# RAB_FM_Birds_3_for_open_bus.net
KiCad netlist of a schematic drawn in EAGLE
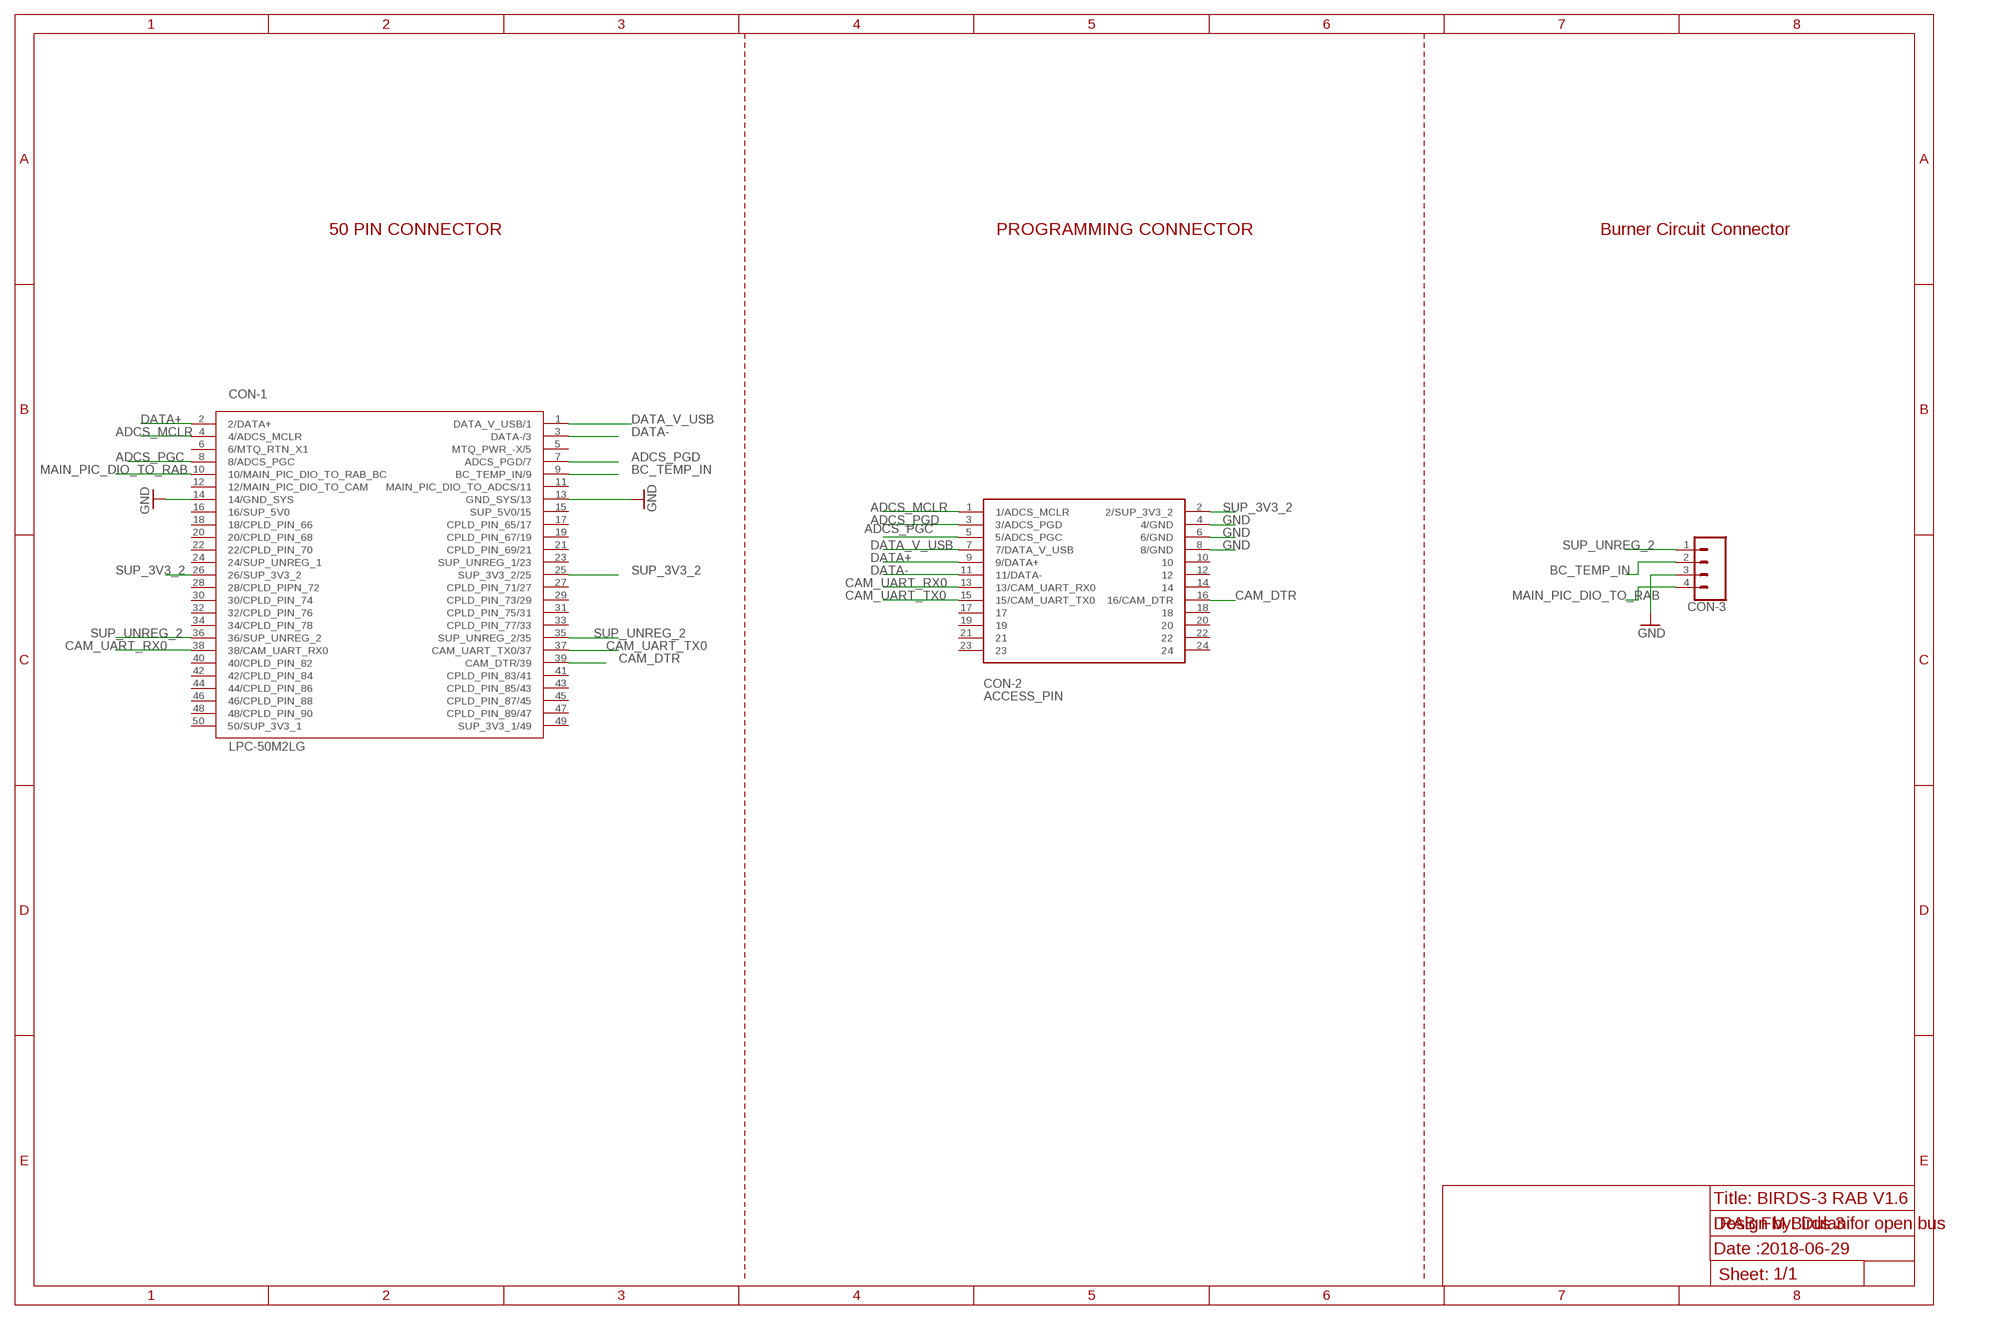
[diagram p0: schematic, sheet 1]

(export (version "E")
  (design (tool "Eeschema 10.0.6"))
  (components
    (comp (ref "CON-1")
      (value "LPC-50M2LG")
      (footprint "eagle-import:LPC-50M2LG")
      (libsource (lib "eagle-import") (part "LPC-50M2LG"))
    )
    (comp (ref "CON-2")
      (value "ACCESS_PIN")
      (footprint "eagle-import:SMD24")
      (libsource (lib "eagle-import") (part "ACCESS_PIN"))
    )
    (comp (ref "CON-3")
      (value "CONN_04JST-PTH")
      (footprint "eagle-import:JST-4-PTH")
      (libsource (lib "eagle-import") (part "CONN_04JST-PTH"))
    )
  )
  (nets
    (net (code "1") (name "/ADCS_MCLR") (class "Default")
      (node (ref "CON-1") (pin "4") (pinfunction "4/ADCS_MCLR_4") (pintype "bidirectional"))
      (node (ref "CON-2") (pin "1") (pinfunction "1/ADCS_MCLR_1") (pintype "bidirectional"))
    )
    (net (code "2") (name "/ADCS_PGC") (class "Default")
      (node (ref "CON-1") (pin "8") (pinfunction "8/ADCS_PGC_8") (pintype "bidirectional"))
      (node (ref "CON-2") (pin "5") (pinfunction "5/ADCS_PGC_5") (pintype "bidirectional"))
    )
    (net (code "3") (name "/ADCS_PGD") (class "Default")
      (node (ref "CON-1") (pin "7") (pinfunction "ADCS_PGD/7_7") (pintype "bidirectional"))
      (node (ref "CON-2") (pin "3") (pinfunction "3/ADCS_PGD_3") (pintype "bidirectional"))
    )
    (net (code "4") (name "/BC_TEMP_IN") (class "Default")
      (node (ref "CON-1") (pin "9") (pinfunction "BC_TEMP_IN/9_9") (pintype "bidirectional"))
      (node (ref "CON-3") (pin "2") (pinfunction "2_2") (pintype "passive"))
    )
    (net (code "5") (name "/CAM_DTR") (class "Default")
      (node (ref "CON-1") (pin "39") (pinfunction "CAM_DTR/39_39") (pintype "bidirectional"))
      (node (ref "CON-2") (pin "16") (pinfunction "16/CAM_DTR_16") (pintype "bidirectional"))
    )
    (net (code "6") (name "/CAM_UART_RX0") (class "Default")
      (node (ref "CON-1") (pin "38") (pinfunction "38/CAM_UART_RX0_38") (pintype "bidirectional"))
      (node (ref "CON-2") (pin "13") (pinfunction "13/CAM_UART_RX0_13") (pintype "bidirectional"))
    )
    (net (code "7") (name "/CAM_UART_TX0") (class "Default")
      (node (ref "CON-1") (pin "37") (pinfunction "CAM_UART_TX0/37_37") (pintype "bidirectional"))
      (node (ref "CON-2") (pin "15") (pinfunction "15/CAM_UART_TX0_15") (pintype "bidirectional"))
    )
    (net (code "8") (name "/DATA+") (class "Default")
      (node (ref "CON-1") (pin "2") (pinfunction "2/DATA+_2") (pintype "bidirectional"))
      (node (ref "CON-2") (pin "9") (pinfunction "9/DATA+_9") (pintype "bidirectional"))
    )
    (net (code "9") (name "/DATA-") (class "Default")
      (node (ref "CON-1") (pin "3") (pinfunction "DATA-/3_3") (pintype "bidirectional"))
      (node (ref "CON-2") (pin "11") (pinfunction "11/DATA-_11") (pintype "bidirectional"))
    )
    (net (code "10") (name "/DATA_V_USB") (class "Default")
      (node (ref "CON-1") (pin "1") (pinfunction "DATA_V_USB/1_1") (pintype "bidirectional"))
      (node (ref "CON-2") (pin "7") (pinfunction "7/DATA_V_USB_7") (pintype "bidirectional"))
    )
    (net (code "11") (name "/MAIN_PIC_DIO_TO_RAB") (class "Default")
      (node (ref "CON-1") (pin "10") (pinfunction "10/MAIN_PIC_DIO_TO_RAB_BC_10") (pintype "bidirectional"))
      (node (ref "CON-3") (pin "4") (pinfunction "4_4") (pintype "passive"))
    )
    (net (code "12") (name "/SUP_3V3_2") (class "Default")
      (node (ref "CON-1") (pin "25") (pinfunction "SUP_3V3_2/25_25") (pintype "bidirectional"))
      (node (ref "CON-1") (pin "26") (pinfunction "26/SUP_3V3_2_26") (pintype "bidirectional"))
      (node (ref "CON-2") (pin "2") (pinfunction "2/SUP_3V3_2_2") (pintype "bidirectional"))
    )
    (net (code "13") (name "/SUP_UNREG_2") (class "Default")
      (node (ref "CON-1") (pin "35") (pinfunction "SUP_UNREG_2/35_35") (pintype "bidirectional"))
      (node (ref "CON-1") (pin "36") (pinfunction "36/SUP_UNREG_2_36") (pintype "bidirectional"))
      (node (ref "CON-3") (pin "1") (pinfunction "1_1") (pintype "passive"))
    )
    (net (code "14") (name "GND") (class "Default")
      (node (ref "CON-1") (pin "13") (pinfunction "GND_SYS/13_13") (pintype "bidirectional"))
      (node (ref "CON-1") (pin "14") (pinfunction "14/GND_SYS_14") (pintype "bidirectional"))
      (node (ref "CON-2") (pin "4") (pinfunction "4/GND_4") (pintype "bidirectional"))
      (node (ref "CON-2") (pin "6") (pinfunction "6/GND_6") (pintype "bidirectional"))
      (node (ref "CON-2") (pin "8") (pinfunction "8/GND_8") (pintype "bidirectional"))
      (node (ref "CON-3") (pin "3") (pinfunction "3_3") (pintype "passive"))
    )
    (net (code "15") (name "unconnected-(CON-1-6{slash}MTQ_RTN_X1-Pad6)") (class "Default")
      (node (ref "CON-1") (pin "6") (pinfunction "6/MTQ_RTN_X1_6") (pintype "bidirectional"))
    )
    (net (code "16") (name "unconnected-(CON-1-12{slash}MAIN_PIC_DIO_TO_CAM-Pad12)") (class "Default")
      (node (ref "CON-1") (pin "12") (pinfunction "12/MAIN_PIC_DIO_TO_CAM_12") (pintype "bidirectional"))
    )
    (net (code "17") (name "unconnected-(CON-1-16{slash}SUP_5V0-Pad16)") (class "Default")
      (node (ref "CON-1") (pin "16") (pinfunction "16/SUP_5V0_16") (pintype "bidirectional"))
    )
    (net (code "18") (name "unconnected-(CON-1-18{slash}CPLD_PIN_66-Pad18)") (class "Default")
      (node (ref "CON-1") (pin "18") (pinfunction "18/CPLD_PIN_66_18") (pintype "bidirectional"))
    )
    (net (code "19") (name "unconnected-(CON-1-20{slash}CPLD_PIN_68-Pad20)") (class "Default")
      (node (ref "CON-1") (pin "20") (pinfunction "20/CPLD_PIN_68_20") (pintype "bidirectional"))
    )
    (net (code "20") (name "unconnected-(CON-1-22{slash}CPLD_PIN_70-Pad22)") (class "Default")
      (node (ref "CON-1") (pin "22") (pinfunction "22/CPLD_PIN_70_22") (pintype "bidirectional"))
    )
    (net (code "21") (name "unconnected-(CON-1-24{slash}SUP_UNREG_1-Pad24)") (class "Default")
      (node (ref "CON-1") (pin "24") (pinfunction "24/SUP_UNREG_1_24") (pintype "bidirectional"))
    )
    (net (code "22") (name "unconnected-(CON-1-28{slash}CPLD_PIPN_72-Pad28)") (class "Default")
      (node (ref "CON-1") (pin "28") (pinfunction "28/CPLD_PIPN_72_28") (pintype "bidirectional"))
    )
    (net (code "23") (name "unconnected-(CON-1-30{slash}CPLD_PIN_74-Pad30)") (class "Default")
      (node (ref "CON-1") (pin "30") (pinfunction "30/CPLD_PIN_74_30") (pintype "bidirectional"))
    )
    (net (code "24") (name "unconnected-(CON-1-32{slash}CPLD_PIN_76-Pad32)") (class "Default")
      (node (ref "CON-1") (pin "32") (pinfunction "32/CPLD_PIN_76_32") (pintype "bidirectional"))
    )
    (net (code "25") (name "unconnected-(CON-1-34{slash}CPLD_PIN_78-Pad34)") (class "Default")
      (node (ref "CON-1") (pin "34") (pinfunction "34/CPLD_PIN_78_34") (pintype "bidirectional"))
    )
    (net (code "26") (name "unconnected-(CON-1-40{slash}CPLD_PIN_82-Pad40)") (class "Default")
      (node (ref "CON-1") (pin "40") (pinfunction "40/CPLD_PIN_82_40") (pintype "bidirectional"))
    )
    (net (code "27") (name "unconnected-(CON-1-42{slash}CPLD_PIN_84-Pad42)") (class "Default")
      (node (ref "CON-1") (pin "42") (pinfunction "42/CPLD_PIN_84_42") (pintype "bidirectional"))
    )
    (net (code "28") (name "unconnected-(CON-1-44{slash}CPLD_PIN_86-Pad44)") (class "Default")
      (node (ref "CON-1") (pin "44") (pinfunction "44/CPLD_PIN_86_44") (pintype "bidirectional"))
    )
    (net (code "29") (name "unconnected-(CON-1-46{slash}CPLD_PIN_88-Pad46)") (class "Default")
      (node (ref "CON-1") (pin "46") (pinfunction "46/CPLD_PIN_88_46") (pintype "bidirectional"))
    )
    (net (code "30") (name "unconnected-(CON-1-48{slash}CPLD_PIN_90-Pad48)") (class "Default")
      (node (ref "CON-1") (pin "48") (pinfunction "48/CPLD_PIN_90_48") (pintype "bidirectional"))
    )
    (net (code "31") (name "unconnected-(CON-1-50{slash}SUP_3V3_1-Pad50)") (class "Default")
      (node (ref "CON-1") (pin "50") (pinfunction "50/SUP_3V3_1_50") (pintype "bidirectional"))
    )
    (net (code "32") (name "unconnected-(CON-1-CPLD_PIN_65{slash}17-Pad17)") (class "Default")
      (node (ref "CON-1") (pin "17") (pinfunction "CPLD_PIN_65/17_17") (pintype "bidirectional"))
    )
    (net (code "33") (name "unconnected-(CON-1-CPLD_PIN_67{slash}19-Pad19)") (class "Default")
      (node (ref "CON-1") (pin "19") (pinfunction "CPLD_PIN_67/19_19") (pintype "bidirectional"))
    )
    (net (code "34") (name "unconnected-(CON-1-CPLD_PIN_69{slash}21-Pad21)") (class "Default")
      (node (ref "CON-1") (pin "21") (pinfunction "CPLD_PIN_69/21_21") (pintype "bidirectional"))
    )
    (net (code "35") (name "unconnected-(CON-1-CPLD_PIN_71{slash}27-Pad27)") (class "Default")
      (node (ref "CON-1") (pin "27") (pinfunction "CPLD_PIN_71/27_27") (pintype "bidirectional"))
    )
    (net (code "36") (name "unconnected-(CON-1-CPLD_PIN_73{slash}29-Pad29)") (class "Default")
      (node (ref "CON-1") (pin "29") (pinfunction "CPLD_PIN_73/29_29") (pintype "bidirectional"))
    )
    (net (code "37") (name "unconnected-(CON-1-CPLD_PIN_75{slash}31-Pad31)") (class "Default")
      (node (ref "CON-1") (pin "31") (pinfunction "CPLD_PIN_75/31_31") (pintype "bidirectional"))
    )
    (net (code "38") (name "unconnected-(CON-1-CPLD_PIN_77{slash}33-Pad33)") (class "Default")
      (node (ref "CON-1") (pin "33") (pinfunction "CPLD_PIN_77/33_33") (pintype "bidirectional"))
    )
    (net (code "39") (name "unconnected-(CON-1-CPLD_PIN_83{slash}41-Pad41)") (class "Default")
      (node (ref "CON-1") (pin "41") (pinfunction "CPLD_PIN_83/41_41") (pintype "bidirectional"))
    )
    (net (code "40") (name "unconnected-(CON-1-CPLD_PIN_85{slash}43-Pad43)") (class "Default")
      (node (ref "CON-1") (pin "43") (pinfunction "CPLD_PIN_85/43_43") (pintype "bidirectional"))
    )
    (net (code "41") (name "unconnected-(CON-1-CPLD_PIN_87{slash}45-Pad45)") (class "Default")
      (node (ref "CON-1") (pin "45") (pinfunction "CPLD_PIN_87/45_45") (pintype "bidirectional"))
    )
    (net (code "42") (name "unconnected-(CON-1-CPLD_PIN_89{slash}47-Pad47)") (class "Default")
      (node (ref "CON-1") (pin "47") (pinfunction "CPLD_PIN_89/47_47") (pintype "bidirectional"))
    )
    (net (code "43") (name "unconnected-(CON-1-MAIN_PIC_DIO_TO_ADCS{slash}11-Pad11)") (class "Default")
      (node (ref "CON-1") (pin "11") (pinfunction "MAIN_PIC_DIO_TO_ADCS/11_11") (pintype "bidirectional"))
    )
    (net (code "44") (name "unconnected-(CON-1-MTQ_PWR_-X{slash}5-Pad5)") (class "Default")
      (node (ref "CON-1") (pin "5") (pinfunction "MTQ_PWR_-X/5_5") (pintype "bidirectional"))
    )
    (net (code "45") (name "unconnected-(CON-1-SUP_3V3_1{slash}49-Pad49)") (class "Default")
      (node (ref "CON-1") (pin "49") (pinfunction "SUP_3V3_1/49_49") (pintype "bidirectional"))
    )
    (net (code "46") (name "unconnected-(CON-1-SUP_5V0{slash}15-Pad15)") (class "Default")
      (node (ref "CON-1") (pin "15") (pinfunction "SUP_5V0/15_15") (pintype "bidirectional"))
    )
    (net (code "47") (name "unconnected-(CON-1-SUP_UNREG_1{slash}23-Pad23)") (class "Default")
      (node (ref "CON-1") (pin "23") (pinfunction "SUP_UNREG_1/23_23") (pintype "bidirectional"))
    )
    (net (code "48") (name "unconnected-(CON-2-Pad10)") (class "Default")
      (node (ref "CON-2") (pin "10") (pinfunction "10_10") (pintype "bidirectional"))
    )
    (net (code "49") (name "unconnected-(CON-2-Pad12)") (class "Default")
      (node (ref "CON-2") (pin "12") (pinfunction "12_12") (pintype "bidirectional"))
    )
    (net (code "50") (name "unconnected-(CON-2-Pad14)") (class "Default")
      (node (ref "CON-2") (pin "14") (pinfunction "14_14") (pintype "bidirectional"))
    )
    (net (code "51") (name "unconnected-(CON-2-Pad17)") (class "Default")
      (node (ref "CON-2") (pin "17") (pinfunction "17_17") (pintype "bidirectional"))
    )
    (net (code "52") (name "unconnected-(CON-2-Pad18)") (class "Default")
      (node (ref "CON-2") (pin "18") (pinfunction "18_18") (pintype "bidirectional"))
    )
    (net (code "53") (name "unconnected-(CON-2-Pad19)") (class "Default")
      (node (ref "CON-2") (pin "19") (pinfunction "19_19") (pintype "bidirectional"))
    )
    (net (code "54") (name "unconnected-(CON-2-Pad20)") (class "Default")
      (node (ref "CON-2") (pin "20") (pinfunction "20_20") (pintype "bidirectional"))
    )
    (net (code "55") (name "unconnected-(CON-2-Pad21)") (class "Default")
      (node (ref "CON-2") (pin "21") (pinfunction "21_21") (pintype "bidirectional"))
    )
    (net (code "56") (name "unconnected-(CON-2-Pad22)") (class "Default")
      (node (ref "CON-2") (pin "22") (pinfunction "22_22") (pintype "bidirectional"))
    )
    (net (code "57") (name "unconnected-(CON-2-Pad23)") (class "Default")
      (node (ref "CON-2") (pin "23") (pinfunction "23_23") (pintype "bidirectional"))
    )
    (net (code "58") (name "unconnected-(CON-2-Pad24)") (class "Default")
      (node (ref "CON-2") (pin "24") (pinfunction "24_24") (pintype "bidirectional"))
    )
  )
)
